# PAGE1.net
KiCad netlist of a schematic drawn in Altium Designer
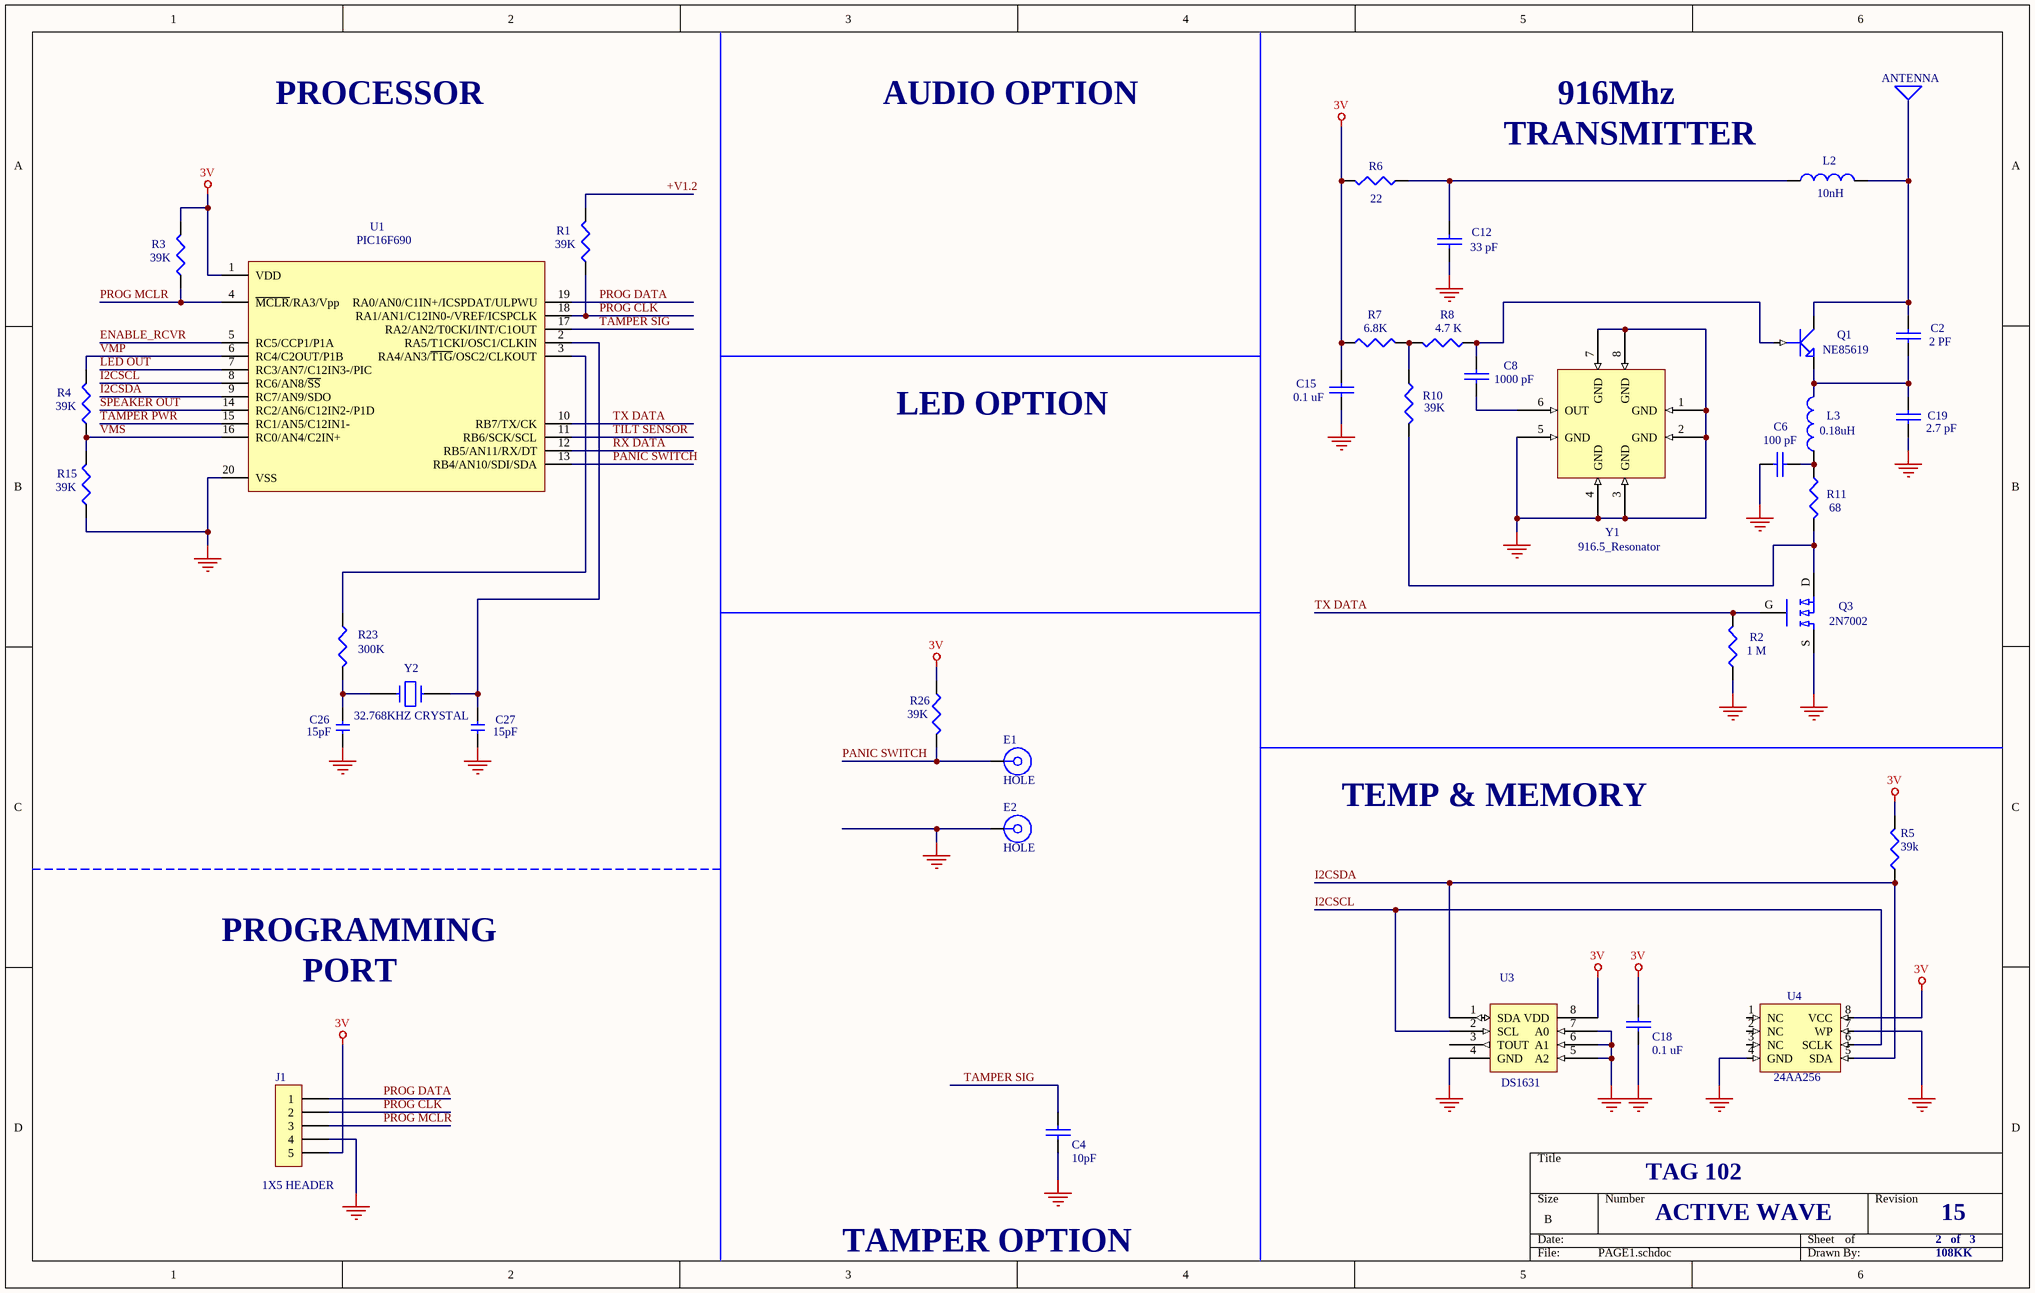
[diagram p0: PAGE1.schdoc]

(export (version "E")
  (design (tool "Eeschema 10.0.6"))
  (components
    (comp (ref "C2")
      (value "2 PF")
      (footprint "0603")
      (description "Capacitor")
      (libsource (lib "*") (part "CAP"))
    )
    (comp (ref "C4")
      (value "10pF")
      (footprint "0603")
      (description "Capacitor")
      (libsource (lib "*") (part "CAP"))
    )
    (comp (ref "C6")
      (value "100 pF")
      (footprint "0603")
      (description "Capacitor")
      (libsource (lib "*") (part "CAP"))
    )
    (comp (ref "C8")
      (value "1000 pF")
      (footprint "0603")
      (description "Capacitor")
      (libsource (lib "*") (part "CAP"))
    )
    (comp (ref "C12")
      (value "33 pF")
      (footprint "0603")
      (description "Capacitor")
      (libsource (lib "*") (part "CAP"))
    )
    (comp (ref "C15")
      (value "0.1 uF")
      (footprint "0603")
      (description "Capacitor")
      (libsource (lib "*") (part "CAP"))
    )
    (comp (ref "C18")
      (value "0.1 uF")
      (footprint "0603")
      (description "Capacitor")
      (libsource (lib "*") (part "CAP"))
    )
    (comp (ref "C19")
      (value "2.7 pF")
      (footprint "0603")
      (description "Capacitor")
      (libsource (lib "*") (part "CAP"))
    )
    (comp (ref "C26") (value "15pF") (footprint "0603") (libsource (lib "*") (part "C")))
    (comp (ref "C27") (value "15pF") (footprint "0603") (libsource (lib "*") (part "C")))
    (comp (ref "E1")
      (value "HOLE")
      (footprint "Holes:EH_D0500P1000")
      (description "DRL 0.50,PAD 1.00-P")
      (fields (field (name "MFR") "0"))
      (libsource (lib "SensormaticDBase") (part "HOLE"))
    )
    (comp (ref "E2")
      (value "HOLE")
      (footprint "Holes:EH_D0500P1000")
      (description "DRL 0.50,PAD 1.00-P")
      (fields (field (name "MFR") "0"))
      (libsource (lib "SensormaticDBase") (part "HOLE"))
    )
    (comp (ref "J1")
      (value "1X5 HEADER")
      (footprint "CONN5")
      (description "Connector")
      (libsource (lib "*") (part "CON5"))
    )
    (comp (ref "L2") (value "10nH") (footprint "0603") (libsource (lib "*") (part "INDUCTOR")))
    (comp (ref "L3") (value "0.18uH") (footprint "0603") (libsource (lib "*") (part "INDUCTOR")))
    (comp (ref "Q1")
      (value "NE85619")
      (footprint "3 PIN ULTRA SUPER MINI MOLD")
      (description "NPN Transistor")
      (libsource (lib "*") (part "NPN1"))
    )
    (comp (ref "Q3") (value "2N7002") (libsource (lib "*") (part "FET 2")))
    (comp (ref "R1") (value "39K") (footprint "0603") (libsource (lib "*") (part "RESISTOR")))
    (comp (ref "R2") (value "1 M") (footprint "0603") (libsource (lib "*") (part "RESISTOR")))
    (comp (ref "R3") (value "39K") (footprint "0603") (libsource (lib "*") (part "RESISTOR")))
    (comp (ref "R4") (value "39K") (footprint "0603") (libsource (lib "*") (part "RESISTOR")))
    (comp (ref "R5") (value "39k") (footprint "0603") (libsource (lib "*") (part "RESISTOR")))
    (comp (ref "R6") (value "22") (footprint "0603") (libsource (lib "*") (part "RESISTOR")))
    (comp (ref "R7") (value "6.8K") (footprint "0603") (libsource (lib "*") (part "RESISTOR")))
    (comp (ref "R8") (value "4.7 K") (footprint "0603") (libsource (lib "*") (part "RESISTOR")))
    (comp (ref "R10") (value "39K") (footprint "0603") (libsource (lib "*") (part "RESISTOR")))
    (comp (ref "R11") (value "68") (footprint "0603") (libsource (lib "*") (part "RES1")))
    (comp (ref "R15") (value "39K") (footprint "0603") (libsource (lib "*") (part "RESISTOR")))
    (comp (ref "R23") (value "300K") (footprint "0603") (libsource (lib "*") (part "RESISTOR")))
    (comp (ref "R26") (value "39K") (footprint "0603") (libsource (lib "*") (part "RESISTOR")))
    (comp (ref "U1") (value "PIC16F690") (libsource (lib "*") (part "PIC16F690")))
    (comp (ref "U3") (value "DS1631") (footprint "SO8 SMALL") (libsource (lib "*") (part "DS1631")))
    (comp (ref "U4") (value "24AA256") (footprint "SO8") (libsource (lib "*") (part "24AA256")))
    (comp (ref "Y1")
      (value "916.5_Resonator")
      (footprint "RESONATOR")
      (libsource (lib "*") (part "RESONATOR"))
    )
    (comp (ref "Y2")
      (value "32.768KHZ CRYSTAL")
      (footprint "CRYSTAL ABRACON ABS07")
      (description "Crystal")
      (libsource (lib "*") (part "CRYSTAL"))
    )
  )
  (nets
    (net (code "1") (name "/+V1.2") (class "Default")
      (node (ref "R1") (pin "2") (pinfunction "2_2") (pintype "passive"))
    )
    (net (code "2") (name "/ENABLE_RCVR") (class "Default")
      (node (ref "U1") (pin "5") (pinfunction "RC5/CCP1/P1A_5") (pintype "passive"))
    )
    (net (code "3") (name "/I2CSCL") (class "Default")
      (node (ref "U1") (pin "8") (pinfunction "RC6/AN8/~{SS}_8") (pintype "passive"))
      (node (ref "U3") (pin "2") (pinfunction "SCL_2") (pintype "input"))
      (node (ref "U4") (pin "6") (pinfunction "SCLK_6") (pintype "input"))
    )
    (net (code "4") (name "/I2CSDA") (class "Default")
      (node (ref "R5") (pin "1") (pinfunction "1_1") (pintype "passive"))
      (node (ref "U1") (pin "9") (pinfunction "RC7/AN9/SDO_9") (pintype "passive"))
      (node (ref "U3") (pin "1") (pinfunction "SDA_1") (pintype "bidirectional"))
      (node (ref "U4") (pin "5") (pinfunction "SDA_5") (pintype "input"))
    )
    (net (code "5") (name "/LED OUT") (class "Default")
      (node (ref "U1") (pin "7") (pinfunction "RC3/AN7/C12IN3-/PIC_7") (pintype "passive"))
    )
    (net (code "6") (name "/PANIC SWITCH") (class "Default")
      (node (ref "E1") (pin "1") (pinfunction "1_1") (pintype "passive"))
      (node (ref "R26") (pin "2") (pinfunction "2_2") (pintype "passive"))
      (node (ref "U1") (pin "13") (pinfunction "RB4/AN10/SDI/SDA_13") (pintype "passive"))
    )
    (net (code "7") (name "/PROG CLK") (class "Default")
      (node (ref "J1") (pin "2") (pinfunction "2_2") (pintype "passive"))
      (node (ref "R1") (pin "1") (pinfunction "1_1") (pintype "passive"))
      (node (ref "U1") (pin "18") (pinfunction "RA1/AN1/C12IN0-/VREF/ICSPCLK_18") (pintype "passive"))
    )
    (net (code "8") (name "/PROG DATA") (class "Default")
      (node (ref "J1") (pin "1") (pinfunction "1_1") (pintype "passive"))
      (node (ref "U1") (pin "19") (pinfunction "RA0/AN0/C1IN+/ICSPDAT/ULPWU_19") (pintype "passive"))
    )
    (net (code "9") (name "/PROG MCLR") (class "Default")
      (node (ref "J1") (pin "3") (pinfunction "3_3") (pintype "passive"))
      (node (ref "R3") (pin "1") (pinfunction "1_1") (pintype "passive"))
      (node (ref "U1") (pin "4") (pinfunction "~{MCLR}/RA3/Vpp_4") (pintype "passive"))
    )
    (net (code "10") (name "/RX DATA") (class "Default")
      (node (ref "U1") (pin "12") (pinfunction "RB5/AN11/RX/DT_12") (pintype "passive"))
    )
    (net (code "11") (name "/SPEAKER OUT") (class "Default")
      (node (ref "U1") (pin "14") (pinfunction "RC2/AN6/C12IN2-/P1D_14") (pintype "passive"))
    )
    (net (code "12") (name "/TAMPER PWR") (class "Default")
      (node (ref "U1") (pin "15") (pinfunction "RC1/AN5/C12IN1-_15") (pintype "passive"))
    )
    (net (code "13") (name "/TAMPER SIG") (class "Default")
      (node (ref "C4") (pin "1") (pinfunction "1_1") (pintype "passive"))
      (node (ref "U1") (pin "17") (pinfunction "RA2/AN2/T0CKI/INT/C1OUT_17") (pintype "passive"))
    )
    (net (code "14") (name "/TILT SENSOR") (class "Default")
      (node (ref "U1") (pin "11") (pinfunction "RB6/SCK/SCL_11") (pintype "passive"))
    )
    (net (code "15") (name "/TX DATA") (class "Default")
      (node (ref "Q3") (pin "G") (pinfunction "G_G") (pintype "passive"))
      (node (ref "R2") (pin "2") (pinfunction "2_2") (pintype "passive"))
      (node (ref "U1") (pin "10") (pinfunction "RB7/TX/CK_10") (pintype "passive"))
    )
    (net (code "16") (name "/VMP") (class "Default")
      (node (ref "R4") (pin "2") (pinfunction "2_2") (pintype "passive"))
      (node (ref "U1") (pin "6") (pinfunction "RC4/C2OUT/P1B_6") (pintype "passive"))
    )
    (net (code "17") (name "/VMS") (class "Default")
      (node (ref "R15") (pin "2") (pinfunction "2_2") (pintype "passive"))
      (node (ref "R4") (pin "1") (pinfunction "1_1") (pintype "passive"))
      (node (ref "U1") (pin "16") (pinfunction "RC0/AN4/C2IN+_16") (pintype "passive"))
    )
    (net (code "18") (name "3V") (class "Default")
      (node (ref "C15") (pin "1") (pinfunction "1_1") (pintype "passive"))
      (node (ref "C18") (pin "1") (pinfunction "1_1") (pintype "passive"))
      (node (ref "J1") (pin "5") (pinfunction "5_5") (pintype "passive"))
      (node (ref "R26") (pin "1") (pinfunction "1_1") (pintype "passive"))
      (node (ref "R3") (pin "2") (pinfunction "2_2") (pintype "passive"))
      (node (ref "R5") (pin "2") (pinfunction "2_2") (pintype "passive"))
      (node (ref "R6") (pin "2") (pinfunction "2_2") (pintype "passive"))
      (node (ref "R7") (pin "1") (pinfunction "1_1") (pintype "passive"))
      (node (ref "U1") (pin "1") (pinfunction "VDD_1") (pintype "passive"))
      (node (ref "U3") (pin "8") (pinfunction "VDD_8") (pintype "power_in"))
      (node (ref "U4") (pin "8") (pinfunction "VCC_8") (pintype "input"))
    )
    (net (code "19") (name "GND") (class "Default")
      (node (ref "C12") (pin "2") (pinfunction "2_2") (pintype "passive"))
      (node (ref "C15") (pin "2") (pinfunction "2_2") (pintype "passive"))
      (node (ref "C18") (pin "2") (pinfunction "2_2") (pintype "passive"))
      (node (ref "C19") (pin "2") (pinfunction "2_2") (pintype "passive"))
      (node (ref "C26") (pin "1") (pinfunction "1_1") (pintype "passive"))
      (node (ref "C27") (pin "1") (pinfunction "1_1") (pintype "passive"))
      (node (ref "C4") (pin "2") (pinfunction "2_2") (pintype "passive"))
      (node (ref "C6") (pin "1") (pinfunction "1_1") (pintype "passive"))
      (node (ref "E2") (pin "1") (pinfunction "1_1") (pintype "passive"))
      (node (ref "J1") (pin "4") (pinfunction "4_4") (pintype "passive"))
      (node (ref "Q3") (pin "S") (pinfunction "S_S") (pintype "passive"))
      (node (ref "R15") (pin "1") (pinfunction "1_1") (pintype "passive"))
      (node (ref "R2") (pin "1") (pinfunction "1_1") (pintype "passive"))
      (node (ref "U1") (pin "20") (pinfunction "VSS_20") (pintype "passive"))
      (node (ref "U3") (pin "4") (pinfunction "GND_4") (pintype "power_in"))
      (node (ref "U3") (pin "5") (pinfunction "A2_5") (pintype "input"))
      (node (ref "U3") (pin "6") (pinfunction "A1_6") (pintype "input"))
      (node (ref "U3") (pin "7") (pinfunction "A0_7") (pintype "input"))
      (node (ref "U4") (pin "4") (pinfunction "GND_4") (pintype "input"))
      (node (ref "U4") (pin "7") (pinfunction "WP_7") (pintype "input"))
      (node (ref "Y1") (pin "1") (pinfunction "GND_1") (pintype "input"))
      (node (ref "Y1") (pin "2") (pinfunction "GND_2") (pintype "input"))
      (node (ref "Y1") (pin "3") (pinfunction "GND_3") (pintype "input"))
      (node (ref "Y1") (pin "4") (pinfunction "GND_4") (pintype "input"))
      (node (ref "Y1") (pin "5") (pinfunction "GND_5") (pintype "input"))
      (node (ref "Y1") (pin "7") (pinfunction "GND_7") (pintype "input"))
      (node (ref "Y1") (pin "8") (pinfunction "GND_8") (pintype "input"))
    )
    (net (code "20") (name "Net-(C2-Pad1)") (class "Default")
      (node (ref "C2") (pin "1") (pinfunction "1_1") (pintype "passive"))
      (node (ref "L2") (pin "2") (pinfunction "2_2") (pintype "passive"))
      (node (ref "Q1") (pin "C") (pinfunction "C_C") (pintype "passive"))
    )
    (net (code "21") (name "Net-(C6-Pad2)") (class "Default")
      (node (ref "C6") (pin "2") (pinfunction "2_2") (pintype "passive"))
      (node (ref "L3") (pin "1") (pinfunction "1_1") (pintype "passive"))
      (node (ref "R11") (pin "1") (pinfunction "1_1") (pintype "passive"))
    )
    (net (code "22") (name "Net-(C8-Pad1)") (class "Default")
      (node (ref "C8") (pin "1") (pinfunction "1_1") (pintype "passive"))
      (node (ref "Q1") (pin "B") (pinfunction "B_B") (pintype "input"))
      (node (ref "R8") (pin "1") (pinfunction "1_1") (pintype "passive"))
    )
    (net (code "23") (name "Net-(C12-Pad1)") (class "Default")
      (node (ref "C12") (pin "1") (pinfunction "1_1") (pintype "passive"))
      (node (ref "L2") (pin "1") (pinfunction "1_1") (pintype "passive"))
      (node (ref "R6") (pin "1") (pinfunction "1_1") (pintype "passive"))
    )
    (net (code "24") (name "Net-(C19-Pad1)") (class "Default")
      (node (ref "C19") (pin "1") (pinfunction "1_1") (pintype "passive"))
      (node (ref "C2") (pin "2") (pinfunction "2_2") (pintype "passive"))
      (node (ref "L3") (pin "2") (pinfunction "2_2") (pintype "passive"))
      (node (ref "Q1") (pin "E") (pinfunction "E_E") (pintype "passive"))
    )
    (net (code "25") (name "Net-(C26-Pad2)") (class "Default")
      (node (ref "C26") (pin "2") (pinfunction "2_2") (pintype "passive"))
      (node (ref "R23") (pin "2") (pinfunction "2_2") (pintype "passive"))
      (node (ref "Y2") (pin "2") (pinfunction "2_2") (pintype "passive"))
    )
    (net (code "26") (name "Net-(Q3-PadD)") (class "Default")
      (node (ref "Q3") (pin "D") (pinfunction "D_D") (pintype "passive"))
      (node (ref "R10") (pin "2") (pinfunction "2_2") (pintype "passive"))
      (node (ref "R11") (pin "2") (pinfunction "2_2") (pintype "passive"))
    )
    (net (code "27") (name "Net-(R10-Pad1)") (class "Default")
      (node (ref "R10") (pin "1") (pinfunction "1_1") (pintype "passive"))
      (node (ref "R7") (pin "2") (pinfunction "2_2") (pintype "passive"))
      (node (ref "R8") (pin "2") (pinfunction "2_2") (pintype "passive"))
    )
    (net (code "28") (name "Net-(U1-RA4{slash}AN3{slash}~{T1G}{slash}OSC2{slash}CLKOUT)") (class "Default")
      (node (ref "R23") (pin "1") (pinfunction "1_1") (pintype "passive"))
      (node (ref "U1") (pin "3") (pinfunction "RA4/AN3/~{T1G}/OSC2/CLKOUT_3") (pintype "passive"))
    )
    (net (code "29") (name "Net-(U1-RA5{slash}T1CKI{slash}OSC1{slash}CLKIN)") (class "Default")
      (node (ref "C27") (pin "2") (pinfunction "2_2") (pintype "passive"))
      (node (ref "U1") (pin "2") (pinfunction "RA5/T1CKI/OSC1/CLKIN_2") (pintype "passive"))
      (node (ref "Y2") (pin "1") (pinfunction "1_1") (pintype "passive"))
    )
    (net (code "30") (name "Net-(Y1-OUT)") (class "Default")
      (node (ref "C8") (pin "2") (pinfunction "2_2") (pintype "passive"))
      (node (ref "Y1") (pin "6") (pinfunction "OUT_6") (pintype "input"))
    )
    (net (code "31") (name "unconnected-(U3-TOUT-Pad3)") (class "Default")
      (node (ref "U3") (pin "3") (pinfunction "TOUT_3") (pintype "output"))
    )
    (net (code "32") (name "unconnected-(U4-NC-Pad1)") (class "Default")
      (node (ref "U4") (pin "1") (pinfunction "NC_1") (pintype "input"))
    )
    (net (code "33") (name "unconnected-(U4-NC-Pad2)") (class "Default")
      (node (ref "U4") (pin "2") (pinfunction "NC_2") (pintype "input"))
    )
    (net (code "34") (name "unconnected-(U4-NC-Pad3)") (class "Default")
      (node (ref "U4") (pin "3") (pinfunction "NC_3") (pintype "input"))
    )
  )
)
